# Sheet1.net
KiCad netlist of a schematic drawn in Altium Designer
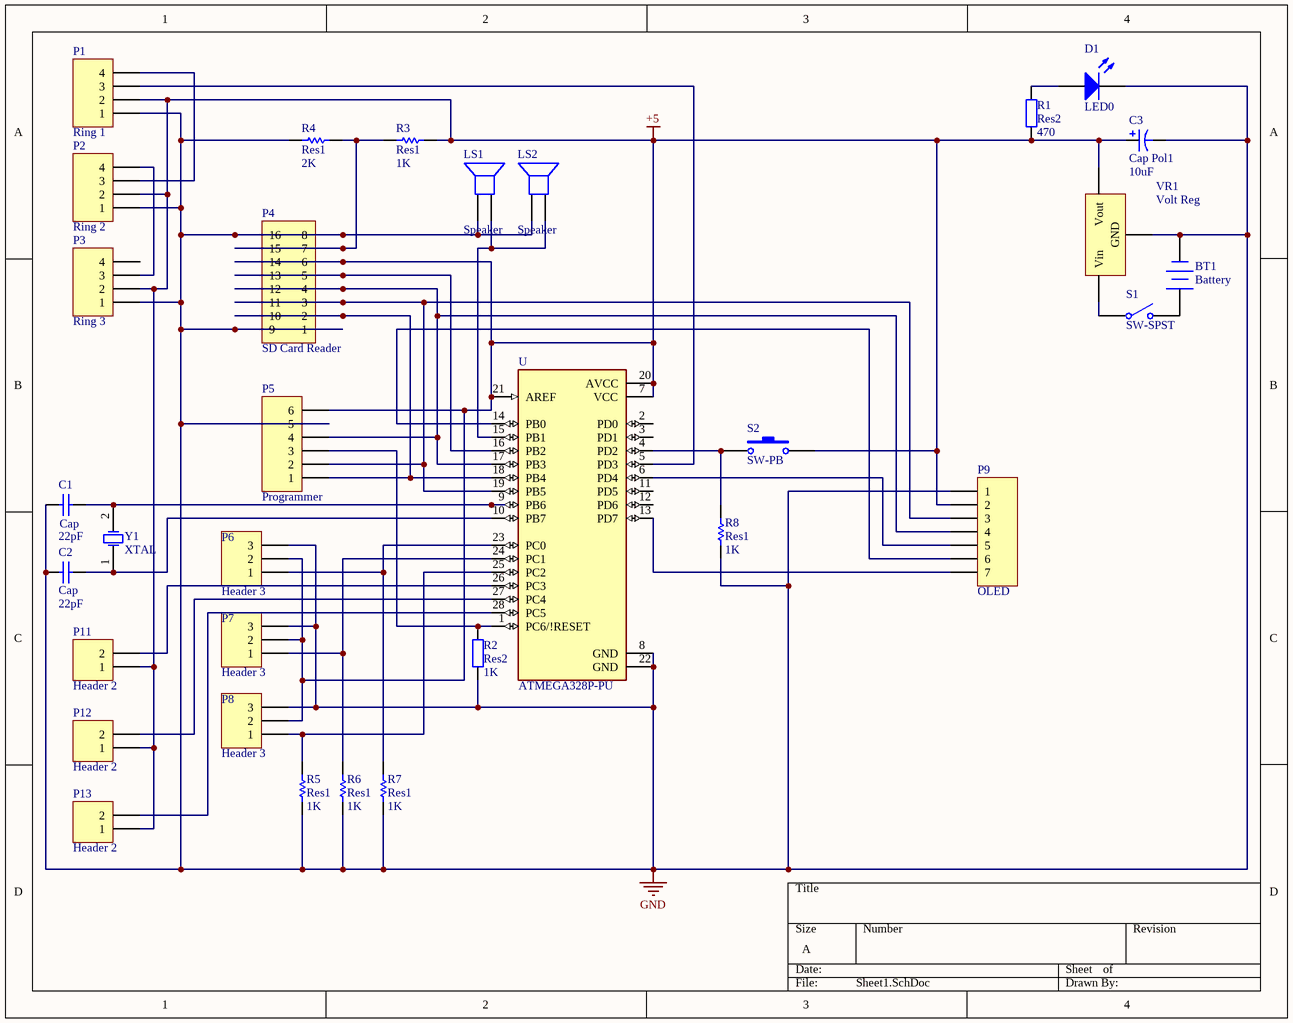
[diagram p0: Sheet1.SchDoc]

(export (version "E")
  (design (tool "Eeschema 10.0.6"))
  (components
    (comp (ref "BT1")
      (value "Battery")
      (footprint "BAT-2")
      (description "Multicell Battery")
      (fields (field (name "PUBLISHER") "Altium Limited"))
      (libsource (lib "Miscellaneous Devices") (part "Battery"))
    )
    (comp (ref "C1")
      (value "Cap")
      (footprint "RAD-0.3")
      (description "Capacitor")
      (fields (field (name "ALTIUM_VALUE") "22pF") (field (name "PUBLISHER") "Altium Limited"))
      (libsource (lib "Miscellaneous Devices") (part "Cap"))
    )
    (comp (ref "C2")
      (value "Cap")
      (footprint "RAD-0.3")
      (description "Capacitor")
      (fields (field (name "ALTIUM_VALUE") "22pF") (field (name "PUBLISHER") "Altium Limited"))
      (libsource (lib "Miscellaneous Devices") (part "Cap"))
    )
    (comp (ref "C3")
      (value "Cap Pol1")
      (footprint "RB7.6-15")
      (description "Polarized Capacitor (Radial)")
      (fields (field (name "ALTIUM_VALUE") "10uF") (field (name "PUBLISHER") "Altium Limited"))
      (libsource (lib "Miscellaneous Devices") (part "Cap Pol1"))
    )
    (comp (ref "D1")
      (value "LED0")
      (footprint "LED-0")
      (description "Typical INFRARED GaAs LED")
      (fields (field (name "PUBLISHER") "Altium Limited"))
      (libsource (lib "Miscellaneous Devices") (part "LED0"))
    )
    (comp (ref "LS1")
      (value "Speaker")
      (footprint "PIN2")
      (description "Loudspeaker")
      (fields (field (name "PUBLISHER") "Altium Limited"))
      (libsource (lib "Miscellaneous Devices") (part "Speaker"))
    )
    (comp (ref "LS2")
      (value "Speaker")
      (footprint "PIN2")
      (description "Loudspeaker")
      (fields (field (name "PUBLISHER") "Altium Limited"))
      (libsource (lib "Miscellaneous Devices") (part "Speaker"))
    )
    (comp (ref "P1")
      (value "Ring 1")
      (footprint "HDR1X4")
      (description "Header, 4-Pin")
      (fields (field (name "PUBLISHER") "Altium Limited"))
      (libsource (lib "Miscellaneous Connectors") (part "Header 4"))
    )
    (comp (ref "P2")
      (value "Ring 2")
      (footprint "HDR1X4")
      (description "Header, 4-Pin")
      (fields (field (name "PUBLISHER") "Altium Limited"))
      (libsource (lib "Miscellaneous Connectors") (part "Header 4"))
    )
    (comp (ref "P3")
      (value "Ring 3")
      (footprint "HDR1X4")
      (description "Header, 4-Pin")
      (fields (field (name "PUBLISHER") "Altium Limited"))
      (libsource (lib "Miscellaneous Connectors") (part "Header 4"))
    )
    (comp (ref "P4")
      (value "SD Card Reader")
      (footprint "HDR2X8_CEN")
      (description "Header, 8-Pin, Dual row")
      (fields (field (name "PUBLISHER") "Altium Limited"))
      (libsource (lib "Miscellaneous Connectors") (part "Header 8X2A"))
    )
    (comp (ref "P5")
      (value "Programmer")
      (footprint "HDR1X6")
      (description "Header, 6-Pin")
      (fields (field (name "PUBLISHER") "Altium Limited"))
      (libsource (lib "Miscellaneous Connectors") (part "Header 6"))
    )
    (comp (ref "P6")
      (value "Header 3")
      (footprint "HDR1X3")
      (description "Header, 3-Pin")
      (fields (field (name "PUBLISHER") "Altium Limited"))
      (libsource (lib "Miscellaneous Connectors") (part "Header 3"))
    )
    (comp (ref "P7")
      (value "Header 3")
      (footprint "HDR1X3")
      (description "Header, 3-Pin")
      (fields (field (name "PUBLISHER") "Altium Limited"))
      (libsource (lib "Miscellaneous Connectors") (part "Header 3"))
    )
    (comp (ref "P8")
      (value "Header 3")
      (footprint "HDR1X3")
      (description "Header, 3-Pin")
      (fields (field (name "PUBLISHER") "Altium Limited"))
      (libsource (lib "Miscellaneous Connectors") (part "Header 3"))
    )
    (comp (ref "P9")
      (value "OLED")
      (footprint "HDR1X7")
      (description "Header, 7-Pin")
      (fields (field (name "PUBLISHER") "Altium Limited"))
      (libsource (lib "Miscellaneous Connectors") (part "Header 7"))
    )
    (comp (ref "P11")
      (value "Header 2")
      (footprint "HDR1X2")
      (description "Header, 2-Pin")
      (fields (field (name "PUBLISHER") "Altium Limited"))
      (libsource (lib "Miscellaneous Connectors") (part "Header 2"))
    )
    (comp (ref "P12")
      (value "Header 2")
      (footprint "HDR1X2")
      (description "Header, 2-Pin")
      (fields (field (name "PUBLISHER") "Altium Limited"))
      (libsource (lib "Miscellaneous Connectors") (part "Header 2"))
    )
    (comp (ref "P13")
      (value "Header 2")
      (footprint "HDR1X2")
      (description "Header, 2-Pin")
      (fields (field (name "PUBLISHER") "Altium Limited"))
      (libsource (lib "Miscellaneous Connectors") (part "Header 2"))
    )
    (comp (ref "R1")
      (value "Res2")
      (footprint "AXIAL-0.4")
      (description "Resistor")
      (fields (field (name "ALTIUM_VALUE") "470") (field (name "PUBLISHER") "Altium Limited"))
      (libsource (lib "") (part "Res2_1"))
    )
    (comp (ref "R2")
      (value "Res2")
      (footprint "AXIAL-0.4")
      (description "Resistor")
      (fields (field (name "ALTIUM_VALUE") "1K") (field (name "PUBLISHER") "Altium Limited"))
      (libsource (lib "Miscellaneous Devices") (part "Res2"))
    )
    (comp (ref "R3")
      (value "Res1")
      (footprint "AXIAL-0.3")
      (description "Resistor")
      (fields (field (name "ALTIUM_VALUE") "1K") (field (name "PUBLISHER") "Altium Limited"))
      (libsource (lib "Miscellaneous Devices") (part "Res1"))
    )
    (comp (ref "R4")
      (value "Res1")
      (footprint "AXIAL-0.3")
      (description "Resistor")
      (fields (field (name "ALTIUM_VALUE") "2K") (field (name "PUBLISHER") "Altium Limited"))
      (libsource (lib "Miscellaneous Devices") (part "Res1"))
    )
    (comp (ref "R5")
      (value "Res1")
      (footprint "AXIAL-0.3")
      (description "Resistor")
      (fields (field (name "ALTIUM_VALUE") "1K") (field (name "PUBLISHER") "Altium Limited"))
      (libsource (lib "Miscellaneous Devices") (part "Res1"))
    )
    (comp (ref "R6")
      (value "Res1")
      (footprint "AXIAL-0.3")
      (description "Resistor")
      (fields (field (name "ALTIUM_VALUE") "1K") (field (name "PUBLISHER") "Altium Limited"))
      (libsource (lib "Miscellaneous Devices") (part "Res1"))
    )
    (comp (ref "R7")
      (value "Res1")
      (footprint "AXIAL-0.3")
      (description "Resistor")
      (fields (field (name "ALTIUM_VALUE") "1K") (field (name "PUBLISHER") "Altium Limited"))
      (libsource (lib "Miscellaneous Devices") (part "Res1"))
    )
    (comp (ref "R8")
      (value "Res1")
      (footprint "AXIAL-0.3")
      (description "Resistor")
      (fields (field (name "ALTIUM_VALUE") "1K") (field (name "PUBLISHER") "Altium Limited"))
      (libsource (lib "Miscellaneous Devices") (part "Res1"))
    )
    (comp (ref "S1")
      (value "SW-SPST")
      (footprint "SPST-2")
      (description "Single-Pole, Single-Throw Switch")
      (fields (field (name "PUBLISHER") "Altium Limited"))
      (libsource (lib "Miscellaneous Devices") (part "SW-SPST"))
    )
    (comp (ref "S2")
      (value "SW-PB")
      (footprint "SPST-2")
      (description "Switch")
      (fields (field (name "PUBLISHER") "Altium Limited"))
      (libsource (lib "Miscellaneous Devices") (part "SW-PB"))
    )
    (comp (ref "U")
      (value "ATMEGA328P-PU")
      (footprint "DIP794W46P254L2967H457Q28B")
      (description "AVR AVRÂ® ATmega Microcontroller IC 8-Bit 20MHz 32KB _16K x 16_ FLASH 28-PDIP")
      (fields (field (name "MF") "Microchip"))
      (libsource (lib "ATMEGA328P-PU") (part "ATMEGA328P-PU"))
    )
    (comp (ref "VR1")
      (value "Volt Reg")
      (footprint "D2PAK_N")
      (description "Voltage Regulator")
      (fields (field (name "PUBLISHER") "Altium Limited"))
      (libsource (lib "Miscellaneous Devices") (part "Volt Reg"))
    )
    (comp (ref "Y1")
      (value "XTAL")
      (footprint "R38")
      (description "Crystal Oscillator")
      (fields (field (name "PUBLISHER") "Altium Limited"))
      (libsource (lib "Miscellaneous Devices") (part "XTAL"))
    )
  )
  (nets
    (net (code "1") (name "+5") (class "Default")
      (node (ref "C3") (pin "1") (pinfunction "1_1") (pintype "passive"))
      (node (ref "P1") (pin "2") (pinfunction "2_2") (pintype "passive"))
      (node (ref "P11") (pin "1") (pinfunction "1_1") (pintype "passive"))
      (node (ref "P12") (pin "1") (pinfunction "1_1") (pintype "passive"))
      (node (ref "P13") (pin "1") (pinfunction "1_1") (pintype "passive"))
      (node (ref "P2") (pin "2") (pinfunction "2_2") (pintype "passive"))
      (node (ref "P3") (pin "2") (pinfunction "2_2") (pintype "passive"))
      (node (ref "P4") (pin "14") (pinfunction "14_14") (pintype "passive"))
      (node (ref "P4") (pin "6") (pinfunction "6_6") (pintype "passive"))
      (node (ref "P5") (pin "6") (pinfunction "6_6") (pintype "passive"))
      (node (ref "P6") (pin "2") (pinfunction "2_2") (pintype "passive"))
      (node (ref "P7") (pin "2") (pinfunction "2_2") (pintype "passive"))
      (node (ref "P8") (pin "2") (pinfunction "2_2") (pintype "passive"))
      (node (ref "P9") (pin "2") (pinfunction "2_2") (pintype "passive"))
      (node (ref "R1") (pin "1") (pinfunction "1_1") (pintype "passive"))
      (node (ref "R3") (pin "2") (pinfunction "2_2") (pintype "passive"))
      (node (ref "S2") (pin "2") (pinfunction "2_2") (pintype "passive"))
      (node (ref "U") (pin "20") (pinfunction "AVCC_20") (pintype "power_in"))
      (node (ref "U") (pin "21") (pinfunction "AREF_21") (pintype "input"))
      (node (ref "U") (pin "7") (pinfunction "VCC_7") (pintype "power_in"))
      (node (ref "VR1") (pin "3") (pinfunction "Vout_3") (pintype "passive"))
    )
    (net (code "2") (name "GND") (class "Default")
      (node (ref "BT1") (pin "2") (pinfunction "-_2") (pintype "passive"))
      (node (ref "C1") (pin "1") (pinfunction "1_1") (pintype "passive"))
      (node (ref "C2") (pin "1") (pinfunction "1_1") (pintype "passive"))
      (node (ref "C3") (pin "2") (pinfunction "2_2") (pintype "passive"))
      (node (ref "D1") (pin "2") (pinfunction "K_2") (pintype "passive"))
      (node (ref "LS1") (pin "1") (pinfunction "1_1") (pintype "passive"))
      (node (ref "LS2") (pin "1") (pinfunction "1_1") (pintype "passive"))
      (node (ref "P1") (pin "1") (pinfunction "1_1") (pintype "passive"))
      (node (ref "P2") (pin "1") (pinfunction "1_1") (pintype "passive"))
      (node (ref "P3") (pin "1") (pinfunction "1_1") (pintype "passive"))
      (node (ref "P4") (pin "1") (pinfunction "1_1") (pintype "passive"))
      (node (ref "P4") (pin "16") (pinfunction "16_16") (pintype "passive"))
      (node (ref "P4") (pin "8") (pinfunction "8_8") (pintype "passive"))
      (node (ref "P4") (pin "9") (pinfunction "9_9") (pintype "passive"))
      (node (ref "P5") (pin "5") (pinfunction "5_5") (pintype "passive"))
      (node (ref "P6") (pin "3") (pinfunction "3_3") (pintype "passive"))
      (node (ref "P7") (pin "3") (pinfunction "3_3") (pintype "passive"))
      (node (ref "P8") (pin "3") (pinfunction "3_3") (pintype "passive"))
      (node (ref "P9") (pin "1") (pinfunction "1_1") (pintype "passive"))
      (node (ref "R2") (pin "2") (pinfunction "2_2") (pintype "passive"))
      (node (ref "R4") (pin "1") (pinfunction "1_1") (pintype "passive"))
      (node (ref "R5") (pin "1") (pinfunction "1_1") (pintype "passive"))
      (node (ref "R6") (pin "1") (pinfunction "1_1") (pintype "passive"))
      (node (ref "R7") (pin "1") (pinfunction "1_1") (pintype "passive"))
      (node (ref "R8") (pin "1") (pinfunction "1_1") (pintype "passive"))
      (node (ref "U") (pin "22") (pinfunction "GND_22") (pintype "power_in"))
      (node (ref "U") (pin "8") (pinfunction "GND_8") (pintype "power_in"))
      (node (ref "VR1") (pin "2") (pinfunction "GND_2") (pintype "passive"))
    )
    (net (code "3") (name "Net-(BT1-+)") (class "Default")
      (node (ref "BT1") (pin "1") (pinfunction "+_1") (pintype "passive"))
      (node (ref "S1") (pin "2") (pinfunction "NO_2") (pintype "passive"))
    )
    (net (code "4") (name "Net-(D1-A)") (class "Default")
      (node (ref "D1") (pin "1") (pinfunction "A_1") (pintype "passive"))
      (node (ref "R1") (pin "2") (pinfunction "2_2") (pintype "passive"))
    )
    (net (code "5") (name "Net-(P1-Pad4)") (class "Default")
      (node (ref "P1") (pin "4") (pinfunction "4_4") (pintype "passive"))
      (node (ref "P2") (pin "3") (pinfunction "3_3") (pintype "passive"))
    )
    (net (code "6") (name "Net-(P2-Pad4)") (class "Default")
      (node (ref "P2") (pin "4") (pinfunction "4_4") (pintype "passive"))
      (node (ref "P3") (pin "3") (pinfunction "3_3") (pintype "passive"))
    )
    (net (code "7") (name "Net-(P4-Pad15)") (class "Default")
      (node (ref "P4") (pin "15") (pinfunction "15_15") (pintype "passive"))
      (node (ref "P4") (pin "7") (pinfunction "7_7") (pintype "passive"))
      (node (ref "R3") (pin "1") (pinfunction "1_1") (pintype "passive"))
      (node (ref "R4") (pin "2") (pinfunction "2_2") (pintype "passive"))
    )
    (net (code "8") (name "Net-(S1-COMMON)") (class "Default")
      (node (ref "S1") (pin "1") (pinfunction "COMMON_1") (pintype "passive"))
      (node (ref "VR1") (pin "1") (pinfunction "Vin_1") (pintype "passive"))
    )
    (net (code "9") (name "Net-(U-PB0)") (class "Default")
      (node (ref "P9") (pin "6") (pinfunction "6_6") (pintype "passive"))
      (node (ref "U") (pin "14") (pinfunction "PB0_14") (pintype "bidirectional"))
    )
    (net (code "10") (name "Net-(U-PB1)") (class "Default")
      (node (ref "LS1") (pin "2") (pinfunction "2_2") (pintype "passive"))
      (node (ref "LS2") (pin "2") (pinfunction "2_2") (pintype "passive"))
      (node (ref "U") (pin "15") (pinfunction "PB1_15") (pintype "bidirectional"))
    )
    (net (code "11") (name "Net-(U-PB2)") (class "Default")
      (node (ref "P4") (pin "13") (pinfunction "13_13") (pintype "passive"))
      (node (ref "P4") (pin "5") (pinfunction "5_5") (pintype "passive"))
      (node (ref "U") (pin "16") (pinfunction "PB2_16") (pintype "bidirectional"))
    )
    (net (code "12") (name "Net-(U-PB3)") (class "Default")
      (node (ref "P4") (pin "12") (pinfunction "12_12") (pintype "passive"))
      (node (ref "P4") (pin "4") (pinfunction "4_4") (pintype "passive"))
      (node (ref "P5") (pin "4") (pinfunction "4_4") (pintype "passive"))
      (node (ref "P9") (pin "4") (pinfunction "4_4") (pintype "passive"))
      (node (ref "U") (pin "17") (pinfunction "PB3_17") (pintype "bidirectional"))
    )
    (net (code "13") (name "Net-(U-PB4)") (class "Default")
      (node (ref "P4") (pin "10") (pinfunction "10_10") (pintype "passive"))
      (node (ref "P4") (pin "2") (pinfunction "2_2") (pintype "passive"))
      (node (ref "P5") (pin "1") (pinfunction "1_1") (pintype "passive"))
      (node (ref "U") (pin "18") (pinfunction "PB4_18") (pintype "bidirectional"))
    )
    (net (code "14") (name "Net-(U-PB5)") (class "Default")
      (node (ref "P4") (pin "11") (pinfunction "11_11") (pintype "passive"))
      (node (ref "P4") (pin "3") (pinfunction "3_3") (pintype "passive"))
      (node (ref "P5") (pin "2") (pinfunction "2_2") (pintype "passive"))
      (node (ref "P9") (pin "3") (pinfunction "3_3") (pintype "passive"))
      (node (ref "U") (pin "19") (pinfunction "PB5_19") (pintype "bidirectional"))
    )
    (net (code "15") (name "Net-(U-PB6)") (class "Default")
      (node (ref "C1") (pin "2") (pinfunction "2_2") (pintype "passive"))
      (node (ref "U") (pin "9") (pinfunction "PB6_9") (pintype "bidirectional"))
      (node (ref "Y1") (pin "2") (pinfunction "OSC2_2") (pintype "passive"))
    )
    (net (code "16") (name "Net-(U-PB7)") (class "Default")
      (node (ref "C2") (pin "2") (pinfunction "2_2") (pintype "passive"))
      (node (ref "U") (pin "10") (pinfunction "PB7_10") (pintype "bidirectional"))
      (node (ref "Y1") (pin "1") (pinfunction "OSC1_1") (pintype "passive"))
    )
    (net (code "17") (name "Net-(U-PC0)") (class "Default")
      (node (ref "P6") (pin "1") (pinfunction "1_1") (pintype "passive"))
      (node (ref "R7") (pin "2") (pinfunction "2_2") (pintype "passive"))
      (node (ref "U") (pin "23") (pinfunction "PC0_23") (pintype "bidirectional"))
    )
    (net (code "18") (name "Net-(U-PC1)") (class "Default")
      (node (ref "P7") (pin "1") (pinfunction "1_1") (pintype "passive"))
      (node (ref "R6") (pin "2") (pinfunction "2_2") (pintype "passive"))
      (node (ref "U") (pin "24") (pinfunction "PC1_24") (pintype "bidirectional"))
    )
    (net (code "19") (name "Net-(U-PC2)") (class "Default")
      (node (ref "P8") (pin "1") (pinfunction "1_1") (pintype "passive"))
      (node (ref "R5") (pin "2") (pinfunction "2_2") (pintype "passive"))
      (node (ref "U") (pin "25") (pinfunction "PC2_25") (pintype "bidirectional"))
    )
    (net (code "20") (name "Net-(U-PC3)") (class "Default")
      (node (ref "P11") (pin "2") (pinfunction "2_2") (pintype "passive"))
      (node (ref "U") (pin "26") (pinfunction "PC3_26") (pintype "bidirectional"))
    )
    (net (code "21") (name "Net-(U-PC4)") (class "Default")
      (node (ref "P12") (pin "2") (pinfunction "2_2") (pintype "passive"))
      (node (ref "U") (pin "27") (pinfunction "PC4_27") (pintype "bidirectional"))
    )
    (net (code "22") (name "Net-(U-PC5)") (class "Default")
      (node (ref "P13") (pin "2") (pinfunction "2_2") (pintype "passive"))
      (node (ref "U") (pin "28") (pinfunction "PC5_28") (pintype "bidirectional"))
    )
    (net (code "23") (name "Net-(U-PC6{slash}!RESET)") (class "Default")
      (node (ref "P5") (pin "3") (pinfunction "3_3") (pintype "passive"))
      (node (ref "R2") (pin "1") (pinfunction "1_1") (pintype "passive"))
      (node (ref "U") (pin "1") (pinfunction "PC6/!RESET_1") (pintype "bidirectional"))
    )
    (net (code "24") (name "Net-(U-PD2)") (class "Default")
      (node (ref "R8") (pin "2") (pinfunction "2_2") (pintype "passive"))
      (node (ref "S2") (pin "1") (pinfunction "1_1") (pintype "passive"))
      (node (ref "U") (pin "4") (pinfunction "PD2_4") (pintype "bidirectional"))
    )
    (net (code "25") (name "Net-(U-PD3)") (class "Default")
      (node (ref "P1") (pin "3") (pinfunction "3_3") (pintype "passive"))
      (node (ref "U") (pin "5") (pinfunction "PD3_5") (pintype "bidirectional"))
    )
    (net (code "26") (name "Net-(U-PD4)") (class "Default")
      (node (ref "P9") (pin "5") (pinfunction "5_5") (pintype "passive"))
      (node (ref "U") (pin "6") (pinfunction "PD4_6") (pintype "bidirectional"))
    )
    (net (code "27") (name "Net-(U-PD7)") (class "Default")
      (node (ref "P9") (pin "7") (pinfunction "7_7") (pintype "passive"))
      (node (ref "U") (pin "13") (pinfunction "PD7_13") (pintype "bidirectional"))
    )
    (net (code "28") (name "unconnected-(P3-Pad4)") (class "Default")
      (node (ref "P3") (pin "4") (pinfunction "4_4") (pintype "passive"))
    )
    (net (code "29") (name "unconnected-(U-PD0-Pad2)") (class "Default")
      (node (ref "U") (pin "2") (pinfunction "PD0_2") (pintype "bidirectional"))
    )
    (net (code "30") (name "unconnected-(U-PD1-Pad3)") (class "Default")
      (node (ref "U") (pin "3") (pinfunction "PD1_3") (pintype "bidirectional"))
    )
    (net (code "31") (name "unconnected-(U-PD5-Pad11)") (class "Default")
      (node (ref "U") (pin "11") (pinfunction "PD5_11") (pintype "bidirectional"))
    )
    (net (code "32") (name "unconnected-(U-PD6-Pad12)") (class "Default")
      (node (ref "U") (pin "12") (pinfunction "PD6_12") (pintype "bidirectional"))
    )
  )
)
